# weichen-a-1.net
KiCad netlist of a schematic drawn in EAGLE
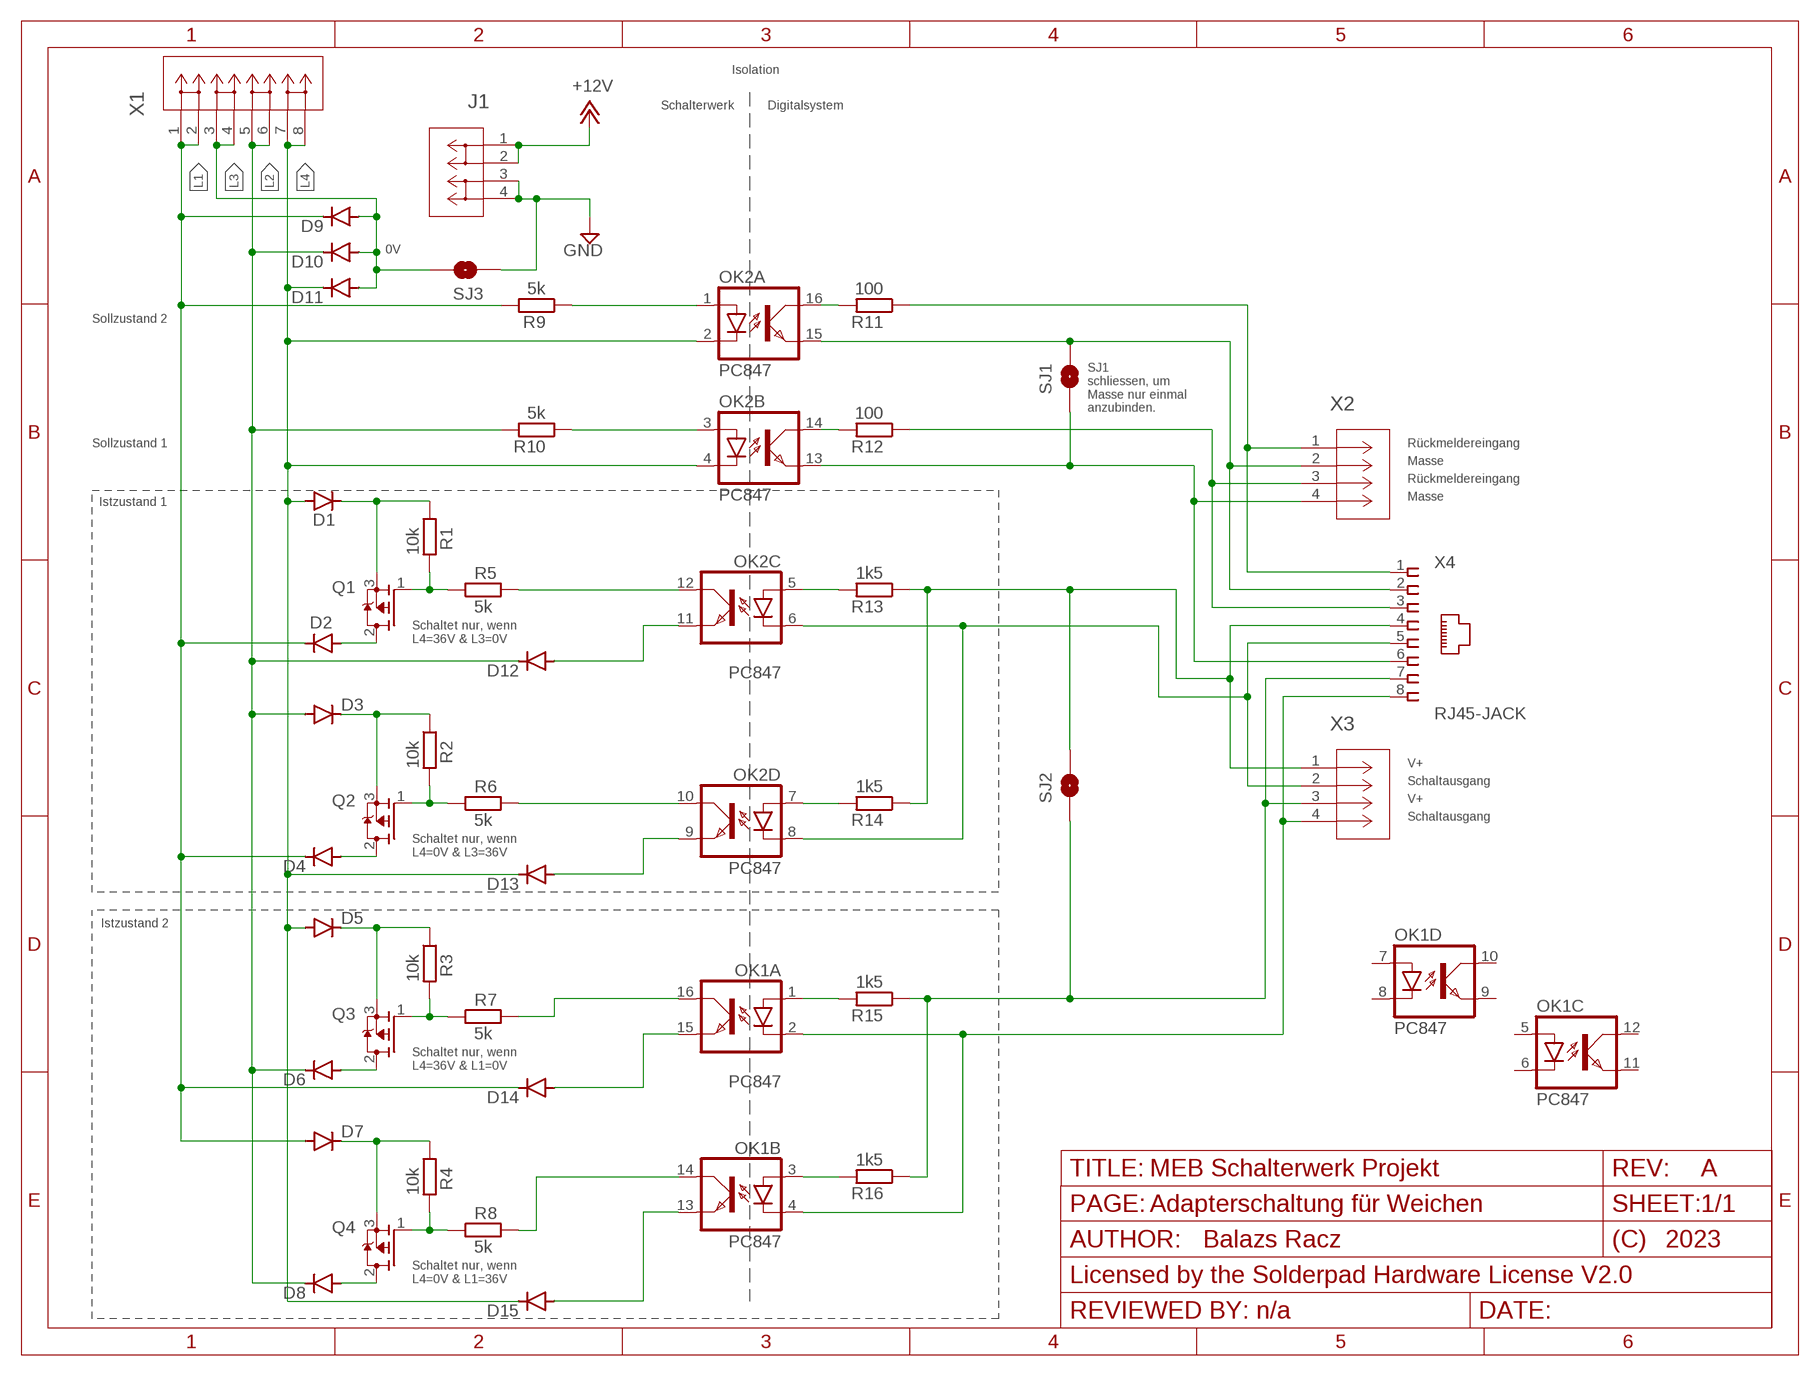
[diagram p0: schematic, sheet 1]

(export (version "E")
  (design (tool "Eeschema 10.0.6"))
  (components
    (comp (ref "D1")
      (value "DIODE-DO214AC")
      (footprint "eagle-import:DO214AC")
      (libsource (lib "eagle-import") (part "DIODE-DO214AC"))
    )
    (comp (ref "D2")
      (value "DIODE-DO214AC")
      (footprint "eagle-import:DO214AC")
      (libsource (lib "eagle-import") (part "DIODE-DO214AC"))
    )
    (comp (ref "D3")
      (value "DIODE-DO214AC")
      (footprint "eagle-import:DO214AC")
      (libsource (lib "eagle-import") (part "DIODE-DO214AC"))
    )
    (comp (ref "D4")
      (value "DIODE-DO214AC")
      (footprint "eagle-import:DO214AC")
      (libsource (lib "eagle-import") (part "DIODE-DO214AC"))
    )
    (comp (ref "D5")
      (value "DIODE-DO214AC")
      (footprint "eagle-import:DO214AC")
      (libsource (lib "eagle-import") (part "DIODE-DO214AC"))
    )
    (comp (ref "D6")
      (value "DIODE-DO214AC")
      (footprint "eagle-import:DO214AC")
      (libsource (lib "eagle-import") (part "DIODE-DO214AC"))
    )
    (comp (ref "D7")
      (value "DIODE-DO214AC")
      (footprint "eagle-import:DO214AC")
      (libsource (lib "eagle-import") (part "DIODE-DO214AC"))
    )
    (comp (ref "D8")
      (value "DIODE-DO214AC")
      (footprint "eagle-import:DO214AC")
      (libsource (lib "eagle-import") (part "DIODE-DO214AC"))
    )
    (comp (ref "D9")
      (value "DIODE-DO214AC")
      (footprint "eagle-import:DO214AC")
      (libsource (lib "eagle-import") (part "DIODE-DO214AC"))
    )
    (comp (ref "D10")
      (value "DIODE-DO214AC")
      (footprint "eagle-import:DO214AC")
      (libsource (lib "eagle-import") (part "DIODE-DO214AC"))
    )
    (comp (ref "D11")
      (value "DIODE-DO214AC")
      (footprint "eagle-import:DO214AC")
      (libsource (lib "eagle-import") (part "DIODE-DO214AC"))
    )
    (comp (ref "D12")
      (value "DIODE-DO214AC")
      (footprint "eagle-import:DO214AC")
      (libsource (lib "eagle-import") (part "DIODE-DO214AC"))
    )
    (comp (ref "D13")
      (value "DIODE-DO214AC")
      (footprint "eagle-import:DO214AC")
      (libsource (lib "eagle-import") (part "DIODE-DO214AC"))
    )
    (comp (ref "D14")
      (value "DIODE-DO214AC")
      (footprint "eagle-import:DO214AC")
      (libsource (lib "eagle-import") (part "DIODE-DO214AC"))
    )
    (comp (ref "D15")
      (value "DIODE-DO214AC")
      (footprint "eagle-import:DO214AC")
      (libsource (lib "eagle-import") (part "DIODE-DO214AC"))
    )
    (comp (ref "J1")
      (value "PHNX_2P_508CONN_1017491")
      (footprint "eagle-import:PHNX_2P_508")
      (fields
        (field (name "MANUFACTURER_PART_NUMBER") "1017503")
        (field (name "COPYRIGHT") "Copyright (C) 2023 Ultra Librarian. All rights reserved.")
      )
      (libsource (lib "eagle-import") (part "PHNX_2P_508CONN_1017491"))
    )
    (comp (ref "OK1")
      (value "PC847")
      (footprint "eagle-import:DIL16")
      (libsource (lib "eagle-import") (part "PC847"))
    )
    (comp (ref "OK2")
      (value "PC847")
      (footprint "eagle-import:DIL16")
      (libsource (lib "eagle-import") (part "PC847"))
    )
    (comp (ref "Q1")
      (value "P-MOSFET")
      (footprint "eagle-import:DPAK-2")
      (fields (field (name "MANUFACTURER") "Infineon"))
      (libsource (lib "eagle-import") (part "P-MOSFET"))
    )
    (comp (ref "Q2")
      (value "P-MOSFET")
      (footprint "eagle-import:DPAK-2")
      (fields (field (name "MANUFACTURER") "Infineon"))
      (libsource (lib "eagle-import") (part "P-MOSFET"))
    )
    (comp (ref "Q3")
      (value "P-MOSFET")
      (footprint "eagle-import:DPAK-2")
      (fields (field (name "MANUFACTURER") "Infineon"))
      (libsource (lib "eagle-import") (part "P-MOSFET"))
    )
    (comp (ref "Q4")
      (value "P-MOSFET")
      (footprint "eagle-import:DPAK-2")
      (fields (field (name "MANUFACTURER") "Infineon"))
      (libsource (lib "eagle-import") (part "P-MOSFET"))
    )
    (comp (ref "R1")
      (value "10k")
      (footprint "eagle-import:R0805")
      (libsource (lib "eagle-import") (part "R-EU_R0805"))
    )
    (comp (ref "R2")
      (value "10k")
      (footprint "eagle-import:R0805")
      (libsource (lib "eagle-import") (part "R-EU_R0805"))
    )
    (comp (ref "R3")
      (value "10k")
      (footprint "eagle-import:R0805")
      (libsource (lib "eagle-import") (part "R-EU_R0805"))
    )
    (comp (ref "R4")
      (value "10k")
      (footprint "eagle-import:R0805")
      (libsource (lib "eagle-import") (part "R-EU_R0805"))
    )
    (comp (ref "R5")
      (value "5k")
      (footprint "eagle-import:R0805")
      (libsource (lib "eagle-import") (part "R-EU_R0805"))
    )
    (comp (ref "R6")
      (value "5k")
      (footprint "eagle-import:R0805")
      (libsource (lib "eagle-import") (part "R-EU_R0805"))
    )
    (comp (ref "R7")
      (value "5k")
      (footprint "eagle-import:R0805")
      (libsource (lib "eagle-import") (part "R-EU_R0805"))
    )
    (comp (ref "R8")
      (value "5k")
      (footprint "eagle-import:R0805")
      (libsource (lib "eagle-import") (part "R-EU_R0805"))
    )
    (comp (ref "R9")
      (value "5k")
      (footprint "eagle-import:R0805")
      (libsource (lib "eagle-import") (part "R-EU_R0805"))
    )
    (comp (ref "R10")
      (value "5k")
      (footprint "eagle-import:R0805")
      (libsource (lib "eagle-import") (part "R-EU_R0805"))
    )
    (comp (ref "R11")
      (value "100")
      (footprint "eagle-import:R0805")
      (libsource (lib "eagle-import") (part "R-EU_R0805"))
    )
    (comp (ref "R12")
      (value "100")
      (footprint "eagle-import:R0805")
      (libsource (lib "eagle-import") (part "R-EU_R0805"))
    )
    (comp (ref "R13")
      (value "1k5")
      (footprint "eagle-import:R0805")
      (libsource (lib "eagle-import") (part "R-EU_R0805"))
    )
    (comp (ref "R14")
      (value "1k5")
      (footprint "eagle-import:R0805")
      (libsource (lib "eagle-import") (part "R-EU_R0805"))
    )
    (comp (ref "R15")
      (value "1k5")
      (footprint "eagle-import:R0805")
      (libsource (lib "eagle-import") (part "R-EU_R0805"))
    )
    (comp (ref "R16")
      (value "1k5")
      (footprint "eagle-import:R0805")
      (libsource (lib "eagle-import") (part "R-EU_R0805"))
    )
    (comp (ref "SJ1")
      (value "SJRND2")
      (footprint "eagle-import:SJ_RND2")
      (libsource (lib "eagle-import") (part "SJRND2"))
    )
    (comp (ref "SJ2")
      (value "SJRND2")
      (footprint "eagle-import:SJ_RND2")
      (libsource (lib "eagle-import") (part "SJRND2"))
    )
    (comp (ref "SJ3")
      (value "SJRND2")
      (footprint "eagle-import:SJ_RND2")
      (libsource (lib "eagle-import") (part "SJRND2"))
    )
    (comp (ref "X1")
      (value "PHNX_4P_508CONN_1017493")
      (footprint "eagle-import:PHNX_4P_508")
      (fields
        (field (name "MANUFACTURER_PART_NUMBER") "1017505")
        (field (name "COPYRIGHT") "Copyright (C) 2023 Ultra Librarian. All rights reserved.")
      )
      (libsource (lib "eagle-import") (part "PHNX_4P_508CONN_1017493"))
    )
    (comp (ref "X2")
      (value "PHNX_4P_350CONN_1984989_PXC")
      (footprint "eagle-import:PHNX_4P_350")
      (fields
        (field (name "MANUFACTURER_PART_NUMBER") "1984989")
        (field (name "COPYRIGHT") "Copyright (C) 2023 Ultra Librarian. All rights reserved.")
      )
      (libsource (lib "eagle-import") (part "PHNX_4P_350CONN_1984989_PXC"))
    )
    (comp (ref "X3")
      (value "PHNX_4P_350CONN_1984989_PXC")
      (footprint "eagle-import:PHNX_4P_350")
      (fields
        (field (name "MANUFACTURER_PART_NUMBER") "1984989")
        (field (name "COPYRIGHT") "Copyright (C) 2023 Ultra Librarian. All rights reserved.")
      )
      (libsource (lib "eagle-import") (part "PHNX_4P_350CONN_1984989_PXC"))
    )
    (comp (ref "X4")
      (value "RJ45-JACK")
      (footprint "eagle-import:RJ45-PULSE-E5J88")
      (libsource (lib "eagle-import") (part "RJ45-JACKRJ45-PULSE-E5J00"))
    )
  )
  (nets
    (net (code "1") (name "+12V") (class "Default")
      (node (ref "J1") (pin "1") (pinfunction "1_1") (pintype "passive"))
      (node (ref "J1") (pin "2") (pinfunction "2_2") (pintype "passive"))
    )
    (net (code "2") (name "GND") (class "Default")
      (node (ref "J1") (pin "3") (pinfunction "3_3") (pintype "passive"))
      (node (ref "J1") (pin "4") (pinfunction "4_4") (pintype "passive"))
      (node (ref "SJ3") (pin "P$1") (pinfunction "1_P$1") (pintype "passive"))
    )
    (net (code "3") (name "L1") (class "Default")
      (node (ref "D14") (pin "C") (pinfunction "C_C") (pintype "passive"))
      (node (ref "D2") (pin "C") (pinfunction "C_C") (pintype "passive"))
      (node (ref "D4") (pin "C") (pinfunction "C_C") (pintype "passive"))
      (node (ref "D7") (pin "A") (pinfunction "A_A") (pintype "passive"))
      (node (ref "D9") (pin "C") (pinfunction "C_C") (pintype "passive"))
      (node (ref "R9") (pin "2") (pinfunction "2_2") (pintype "passive"))
      (node (ref "X1") (pin "1") (pinfunction "1_1") (pintype "passive"))
      (node (ref "X1") (pin "2") (pinfunction "2_2") (pintype "passive"))
    )
    (net (code "4") (name "L2") (class "Default")
      (node (ref "D10") (pin "C") (pinfunction "C_C") (pintype "passive"))
      (node (ref "D12") (pin "C") (pinfunction "C_C") (pintype "passive"))
      (node (ref "D3") (pin "A") (pinfunction "A_A") (pintype "passive"))
      (node (ref "D6") (pin "C") (pinfunction "C_C") (pintype "passive"))
      (node (ref "D8") (pin "C") (pinfunction "C_C") (pintype "passive"))
      (node (ref "R10") (pin "2") (pinfunction "2_2") (pintype "passive"))
      (node (ref "X1") (pin "5") (pinfunction "5_5") (pintype "passive"))
      (node (ref "X1") (pin "6") (pinfunction "6_6") (pintype "passive"))
    )
    (net (code "5") (name "L3") (class "Default")
      (node (ref "D10") (pin "A") (pinfunction "A_A") (pintype "passive"))
      (node (ref "D11") (pin "A") (pinfunction "A_A") (pintype "passive"))
      (node (ref "D9") (pin "A") (pinfunction "A_A") (pintype "passive"))
      (node (ref "SJ3") (pin "P$2") (pinfunction "2_P$2") (pintype "passive"))
      (node (ref "X1") (pin "3") (pinfunction "3_3") (pintype "passive"))
      (node (ref "X1") (pin "4") (pinfunction "4_4") (pintype "passive"))
    )
    (net (code "6") (name "L4") (class "Default")
      (node (ref "D1") (pin "A") (pinfunction "A_A") (pintype "passive"))
      (node (ref "D11") (pin "C") (pinfunction "C_C") (pintype "passive"))
      (node (ref "D13") (pin "C") (pinfunction "C_C") (pintype "passive"))
      (node (ref "D15") (pin "C") (pinfunction "C_C") (pintype "passive"))
      (node (ref "D5") (pin "A") (pinfunction "A_A") (pintype "passive"))
      (node (ref "OK2") (pin "2") (pinfunction "C_2") (pintype "passive"))
      (node (ref "OK2") (pin "4") (pinfunction "C_4") (pintype "passive"))
      (node (ref "X1") (pin "7") (pinfunction "7_7") (pintype "passive"))
      (node (ref "X1") (pin "8") (pinfunction "8_8") (pintype "passive"))
    )
    (net (code "7") (name "Net-(OK1A-A)") (class "Default")
      (node (ref "OK1") (pin "1") (pinfunction "A_1") (pintype "passive"))
      (node (ref "R15") (pin "2") (pinfunction "2_2") (pintype "passive"))
    )
    (net (code "8") (name "Net-(OK1A-C)") (class "Default")
      (node (ref "OK1") (pin "2") (pinfunction "C_2") (pintype "passive"))
      (node (ref "OK1") (pin "4") (pinfunction "C_4") (pintype "passive"))
      (node (ref "X3") (pin "4") (pinfunction "4_4") (pintype "passive"))
      (node (ref "X4") (pin "8") (pinfunction "8_8") (pintype "passive"))
    )
    (net (code "9") (name "Net-(OK1A-COL)") (class "Default")
      (node (ref "OK1") (pin "16") (pinfunction "COL_16") (pintype "passive"))
      (node (ref "R7") (pin "2") (pinfunction "2_2") (pintype "passive"))
    )
    (net (code "10") (name "Net-(OK1A-EMIT)") (class "Default")
      (node (ref "D14") (pin "A") (pinfunction "A_A") (pintype "passive"))
      (node (ref "OK1") (pin "15") (pinfunction "EMIT_15") (pintype "passive"))
    )
    (net (code "11") (name "Net-(OK1B-A)") (class "Default")
      (node (ref "OK1") (pin "3") (pinfunction "A_3") (pintype "passive"))
      (node (ref "R16") (pin "2") (pinfunction "2_2") (pintype "passive"))
    )
    (net (code "12") (name "Net-(OK1B-COL)") (class "Default")
      (node (ref "OK1") (pin "14") (pinfunction "COL_14") (pintype "passive"))
      (node (ref "R8") (pin "2") (pinfunction "2_2") (pintype "passive"))
    )
    (net (code "13") (name "Net-(OK1B-EMIT)") (class "Default")
      (node (ref "D15") (pin "A") (pinfunction "A_A") (pintype "passive"))
      (node (ref "OK1") (pin "13") (pinfunction "EMIT_13") (pintype "passive"))
    )
    (net (code "14") (name "Net-(OK2A-A)") (class "Default")
      (node (ref "OK2") (pin "1") (pinfunction "A_1") (pintype "passive"))
      (node (ref "R9") (pin "1") (pinfunction "1_1") (pintype "passive"))
    )
    (net (code "15") (name "Net-(OK2A-COL)") (class "Default")
      (node (ref "OK2") (pin "16") (pinfunction "COL_16") (pintype "passive"))
      (node (ref "R11") (pin "2") (pinfunction "2_2") (pintype "passive"))
    )
    (net (code "16") (name "Net-(OK2A-EMIT)") (class "Default")
      (node (ref "OK2") (pin "15") (pinfunction "EMIT_15") (pintype "passive"))
      (node (ref "SJ1") (pin "P$2") (pinfunction "2_P$2") (pintype "passive"))
      (node (ref "X2") (pin "2") (pinfunction "2_2") (pintype "passive"))
      (node (ref "X4") (pin "2") (pinfunction "2_2") (pintype "passive"))
    )
    (net (code "17") (name "Net-(OK2B-A)") (class "Default")
      (node (ref "OK2") (pin "3") (pinfunction "A_3") (pintype "passive"))
      (node (ref "R10") (pin "1") (pinfunction "1_1") (pintype "passive"))
    )
    (net (code "18") (name "Net-(OK2B-COL)") (class "Default")
      (node (ref "OK2") (pin "14") (pinfunction "COL_14") (pintype "passive"))
      (node (ref "R12") (pin "2") (pinfunction "2_2") (pintype "passive"))
    )
    (net (code "19") (name "Net-(OK2B-EMIT)") (class "Default")
      (node (ref "OK2") (pin "13") (pinfunction "EMIT_13") (pintype "passive"))
      (node (ref "SJ1") (pin "P$1") (pinfunction "1_P$1") (pintype "passive"))
      (node (ref "X2") (pin "4") (pinfunction "4_4") (pintype "passive"))
      (node (ref "X4") (pin "6") (pinfunction "6_6") (pintype "passive"))
    )
    (net (code "20") (name "Net-(OK2C-A)") (class "Default")
      (node (ref "OK2") (pin "5") (pinfunction "A_5") (pintype "passive"))
      (node (ref "R13") (pin "2") (pinfunction "2_2") (pintype "passive"))
    )
    (net (code "21") (name "Net-(OK2C-C)") (class "Default")
      (node (ref "OK2") (pin "6") (pinfunction "C_6") (pintype "passive"))
      (node (ref "OK2") (pin "8") (pinfunction "C_8") (pintype "passive"))
      (node (ref "X3") (pin "2") (pinfunction "2_2") (pintype "passive"))
      (node (ref "X4") (pin "5") (pinfunction "5_5") (pintype "passive"))
    )
    (net (code "22") (name "Net-(OK2C-COL)") (class "Default")
      (node (ref "OK2") (pin "12") (pinfunction "COL_12") (pintype "passive"))
      (node (ref "R5") (pin "2") (pinfunction "2_2") (pintype "passive"))
    )
    (net (code "23") (name "Net-(OK2C-EMIT)") (class "Default")
      (node (ref "D12") (pin "A") (pinfunction "A_A") (pintype "passive"))
      (node (ref "OK2") (pin "11") (pinfunction "EMIT_11") (pintype "passive"))
    )
    (net (code "24") (name "Net-(OK2D-A)") (class "Default")
      (node (ref "OK2") (pin "7") (pinfunction "A_7") (pintype "passive"))
      (node (ref "R14") (pin "2") (pinfunction "2_2") (pintype "passive"))
    )
    (net (code "25") (name "Net-(OK2D-COL)") (class "Default")
      (node (ref "OK2") (pin "10") (pinfunction "COL_10") (pintype "passive"))
      (node (ref "R6") (pin "2") (pinfunction "2_2") (pintype "passive"))
    )
    (net (code "26") (name "Net-(OK2D-EMIT)") (class "Default")
      (node (ref "D13") (pin "A") (pinfunction "A_A") (pintype "passive"))
      (node (ref "OK2") (pin "9") (pinfunction "EMIT_9") (pintype "passive"))
    )
    (net (code "27") (name "Net-(Q1-D)") (class "Default")
      (node (ref "D2") (pin "A") (pinfunction "A_A") (pintype "passive"))
      (node (ref "Q1") (pin "2") (pinfunction "D_2") (pintype "passive"))
    )
    (net (code "28") (name "Net-(Q1-G)") (class "Default")
      (node (ref "Q1") (pin "1") (pinfunction "G_1") (pintype "passive"))
      (node (ref "R1") (pin "2") (pinfunction "2_2") (pintype "passive"))
      (node (ref "R5") (pin "1") (pinfunction "1_1") (pintype "passive"))
    )
    (net (code "29") (name "Net-(Q1-S)") (class "Default")
      (node (ref "D1") (pin "C") (pinfunction "C_C") (pintype "passive"))
      (node (ref "Q1") (pin "3") (pinfunction "S_3") (pintype "passive"))
      (node (ref "R1") (pin "1") (pinfunction "1_1") (pintype "passive"))
    )
    (net (code "30") (name "Net-(Q2-D)") (class "Default")
      (node (ref "D4") (pin "A") (pinfunction "A_A") (pintype "passive"))
      (node (ref "Q2") (pin "2") (pinfunction "D_2") (pintype "passive"))
    )
    (net (code "31") (name "Net-(Q2-G)") (class "Default")
      (node (ref "Q2") (pin "1") (pinfunction "G_1") (pintype "passive"))
      (node (ref "R2") (pin "2") (pinfunction "2_2") (pintype "passive"))
      (node (ref "R6") (pin "1") (pinfunction "1_1") (pintype "passive"))
    )
    (net (code "32") (name "Net-(Q2-S)") (class "Default")
      (node (ref "D3") (pin "C") (pinfunction "C_C") (pintype "passive"))
      (node (ref "Q2") (pin "3") (pinfunction "S_3") (pintype "passive"))
      (node (ref "R2") (pin "1") (pinfunction "1_1") (pintype "passive"))
    )
    (net (code "33") (name "Net-(Q3-D)") (class "Default")
      (node (ref "D6") (pin "A") (pinfunction "A_A") (pintype "passive"))
      (node (ref "Q3") (pin "2") (pinfunction "D_2") (pintype "passive"))
    )
    (net (code "34") (name "Net-(Q3-G)") (class "Default")
      (node (ref "Q3") (pin "1") (pinfunction "G_1") (pintype "passive"))
      (node (ref "R3") (pin "2") (pinfunction "2_2") (pintype "passive"))
      (node (ref "R7") (pin "1") (pinfunction "1_1") (pintype "passive"))
    )
    (net (code "35") (name "Net-(Q3-S)") (class "Default")
      (node (ref "D5") (pin "C") (pinfunction "C_C") (pintype "passive"))
      (node (ref "Q3") (pin "3") (pinfunction "S_3") (pintype "passive"))
      (node (ref "R3") (pin "1") (pinfunction "1_1") (pintype "passive"))
    )
    (net (code "36") (name "Net-(Q4-D)") (class "Default")
      (node (ref "D8") (pin "A") (pinfunction "A_A") (pintype "passive"))
      (node (ref "Q4") (pin "2") (pinfunction "D_2") (pintype "passive"))
    )
    (net (code "37") (name "Net-(Q4-G)") (class "Default")
      (node (ref "Q4") (pin "1") (pinfunction "G_1") (pintype "passive"))
      (node (ref "R4") (pin "2") (pinfunction "2_2") (pintype "passive"))
      (node (ref "R8") (pin "1") (pinfunction "1_1") (pintype "passive"))
    )
    (net (code "38") (name "Net-(Q4-S)") (class "Default")
      (node (ref "D7") (pin "C") (pinfunction "C_C") (pintype "passive"))
      (node (ref "Q4") (pin "3") (pinfunction "S_3") (pintype "passive"))
      (node (ref "R4") (pin "1") (pinfunction "1_1") (pintype "passive"))
    )
    (net (code "39") (name "Net-(R11-Pad1)") (class "Default")
      (node (ref "R11") (pin "1") (pinfunction "1_1") (pintype "passive"))
      (node (ref "X2") (pin "1") (pinfunction "1_1") (pintype "passive"))
      (node (ref "X4") (pin "1") (pinfunction "1_1") (pintype "passive"))
    )
    (net (code "40") (name "Net-(R12-Pad1)") (class "Default")
      (node (ref "R12") (pin "1") (pinfunction "1_1") (pintype "passive"))
      (node (ref "X2") (pin "3") (pinfunction "3_3") (pintype "passive"))
      (node (ref "X4") (pin "3") (pinfunction "3_3") (pintype "passive"))
    )
    (net (code "41") (name "Net-(SJ2-1)") (class "Default")
      (node (ref "R15") (pin "1") (pinfunction "1_1") (pintype "passive"))
      (node (ref "R16") (pin "1") (pinfunction "1_1") (pintype "passive"))
      (node (ref "SJ2") (pin "P$1") (pinfunction "1_P$1") (pintype "passive"))
      (node (ref "X3") (pin "3") (pinfunction "3_3") (pintype "passive"))
      (node (ref "X4") (pin "7") (pinfunction "7_7") (pintype "passive"))
    )
    (net (code "42") (name "Net-(SJ2-2)") (class "Default")
      (node (ref "R13") (pin "1") (pinfunction "1_1") (pintype "passive"))
      (node (ref "R14") (pin "1") (pinfunction "1_1") (pintype "passive"))
      (node (ref "SJ2") (pin "P$2") (pinfunction "2_P$2") (pintype "passive"))
      (node (ref "X3") (pin "1") (pinfunction "1_1") (pintype "passive"))
      (node (ref "X4") (pin "4") (pinfunction "4_4") (pintype "passive"))
    )
    (net (code "43") (name "unconnected-(OK1C-A-Pad5)") (class "Default")
      (node (ref "OK1") (pin "5") (pinfunction "A_5") (pintype "passive"))
    )
    (net (code "44") (name "unconnected-(OK1C-C-Pad6)") (class "Default")
      (node (ref "OK1") (pin "6") (pinfunction "C_6") (pintype "passive"))
    )
    (net (code "45") (name "unconnected-(OK1C-COL-Pad12)") (class "Default")
      (node (ref "OK1") (pin "12") (pinfunction "COL_12") (pintype "passive"))
    )
    (net (code "46") (name "unconnected-(OK1C-EMIT-Pad11)") (class "Default")
      (node (ref "OK1") (pin "11") (pinfunction "EMIT_11") (pintype "passive"))
    )
    (net (code "47") (name "unconnected-(OK1D-A-Pad7)") (class "Default")
      (node (ref "OK1") (pin "7") (pinfunction "A_7") (pintype "passive"))
    )
    (net (code "48") (name "unconnected-(OK1D-C-Pad8)") (class "Default")
      (node (ref "OK1") (pin "8") (pinfunction "C_8") (pintype "passive"))
    )
    (net (code "49") (name "unconnected-(OK1D-COL-Pad10)") (class "Default")
      (node (ref "OK1") (pin "10") (pinfunction "COL_10") (pintype "passive"))
    )
    (net (code "50") (name "unconnected-(OK1D-EMIT-Pad9)") (class "Default")
      (node (ref "OK1") (pin "9") (pinfunction "EMIT_9") (pintype "passive"))
    )
  )
)
